# output_stage.net
KiCad netlist of a schematic drawn in EAGLE
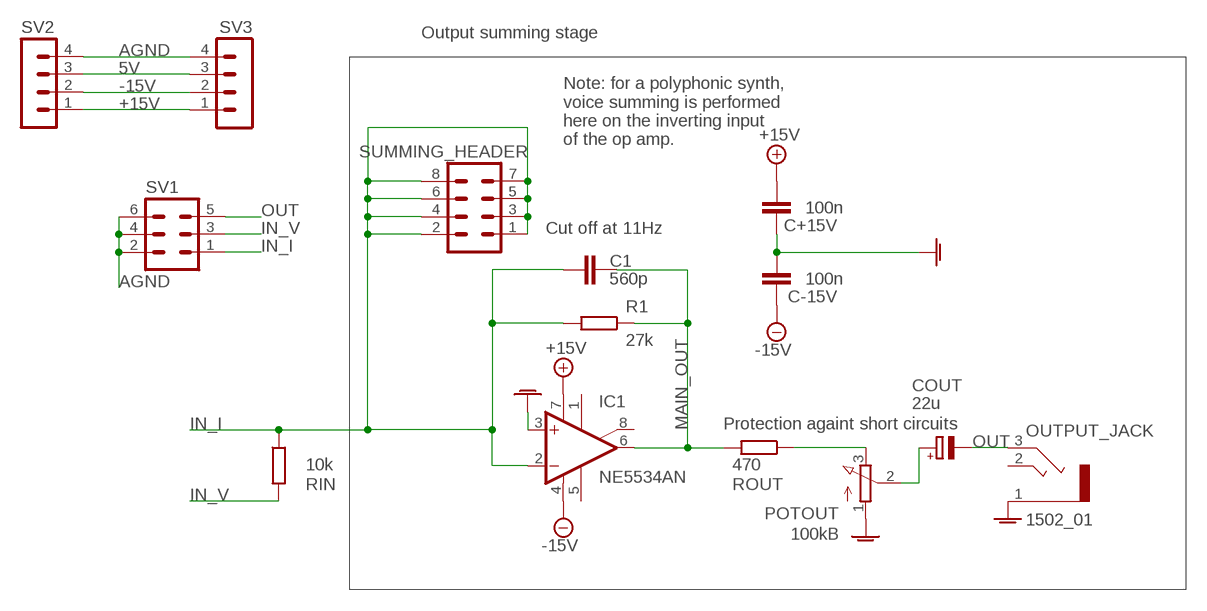
[diagram p0: schematic, sheet 1]

(export (version "E")
  (design (tool "Eeschema 10.0.6"))
  (components
    (comp (ref "C+15V")
      (value "100n")
      (footprint "eagle-import:C075-032X103")
      (libsource (lib "eagle-import") (part "C-EU075-032X103"))
    )
    (comp (ref "C-15V")
      (value "100n")
      (footprint "eagle-import:C075-032X103")
      (libsource (lib "eagle-import") (part "C-EU075-032X103"))
    )
    (comp (ref "C1")
      (value "560p")
      (footprint "eagle-import:C075-032X103")
      (libsource (lib "eagle-import") (part "C-EU075-032X103"))
    )
    (comp (ref "COUT")
      (value "22u")
      (footprint "eagle-import:B45181A")
      (libsource (lib "eagle-import") (part "CPOL-EUB45181A"))
    )
    (comp (ref "IC1")
      (value "NE5534AN")
      (footprint "eagle-import:DIL08")
      (libsource (lib "eagle-import") (part "NE5534NA"))
    )
    (comp (ref "OUTPUT_JACK")
      (value "1502_01")
      (footprint "eagle-import:1502_01")
      (libsource (lib "eagle-import") (part "1502_01"))
    )
    (comp (ref "POTOUT")
      (value "100kB")
      (footprint "eagle-import:3RP_1610N")
      (libsource (lib "eagle-import") (part "3RP/1610N"))
    )
    (comp (ref "R1")
      (value "27k")
      (footprint "eagle-import:0207_10")
      (libsource (lib "eagle-import") (part "R-EU_0207/10"))
    )
    (comp (ref "RIN")
      (value "10k")
      (footprint "eagle-import:0207_10")
      (libsource (lib "eagle-import") (part "R-EU_0207/10"))
    )
    (comp (ref "ROUT")
      (value "470")
      (footprint "eagle-import:0207_12")
      (libsource (lib "eagle-import") (part "R-EU_0207/12"))
    )
    (comp (ref "SUMMING_HEADER")
      (value "MA04-2")
      (footprint "eagle-import:MA04-2")
      (libsource (lib "eagle-import") (part "MA04-2"))
    )
    (comp (ref "SV1")
      (value "MA03-2")
      (footprint "eagle-import:MA03-2")
      (libsource (lib "eagle-import") (part "MA03-2"))
    )
    (comp (ref "SV2")
      (value "MA04-1")
      (footprint "eagle-import:MA04-1")
      (libsource (lib "eagle-import") (part "MA04-1"))
    )
    (comp (ref "SV3")
      (value "MA04-1")
      (footprint "eagle-import:MA04-1")
      (libsource (lib "eagle-import") (part "MA04-1"))
    )
  )
  (nets
    (net (code "1") (name "+15V") (class "Default")
      (node (ref "C+15V") (pin "2") (pinfunction "2_2") (pintype "passive"))
      (node (ref "IC1") (pin "7") (pinfunction "V+_7") (pintype "power_in"))
      (node (ref "SV2") (pin "1") (pinfunction "1_1") (pintype "passive"))
      (node (ref "SV3") (pin "1") (pinfunction "1_1") (pintype "passive"))
    )
    (net (code "2") (name "-15V") (class "Default")
      (node (ref "C-15V") (pin "1") (pinfunction "1_1") (pintype "passive"))
      (node (ref "IC1") (pin "4") (pinfunction "V-_4") (pintype "power_in"))
      (node (ref "SV2") (pin "2") (pinfunction "2_2") (pintype "passive"))
      (node (ref "SV3") (pin "2") (pinfunction "2_2") (pintype "passive"))
    )
    (net (code "3") (name "/5V") (class "Default")
      (node (ref "SV2") (pin "3") (pinfunction "3_3") (pintype "passive"))
      (node (ref "SV3") (pin "3") (pinfunction "3_3") (pintype "passive"))
    )
    (net (code "4") (name "/IN_I") (class "Default")
      (node (ref "C1") (pin "2") (pinfunction "2_2") (pintype "passive"))
      (node (ref "IC1") (pin "2") (pinfunction "-IN_2") (pintype "input"))
      (node (ref "R1") (pin "2") (pinfunction "2_2") (pintype "passive"))
      (node (ref "RIN") (pin "1") (pinfunction "1_1") (pintype "passive"))
      (node (ref "SUMMING_HEADER") (pin "1") (pinfunction "1_1") (pintype "passive"))
      (node (ref "SUMMING_HEADER") (pin "2") (pinfunction "2_2") (pintype "passive"))
      (node (ref "SUMMING_HEADER") (pin "3") (pinfunction "3_3") (pintype "passive"))
      (node (ref "SUMMING_HEADER") (pin "4") (pinfunction "4_4") (pintype "passive"))
      (node (ref "SUMMING_HEADER") (pin "5") (pinfunction "5_5") (pintype "passive"))
      (node (ref "SUMMING_HEADER") (pin "6") (pinfunction "6_6") (pintype "passive"))
      (node (ref "SUMMING_HEADER") (pin "7") (pinfunction "7_7") (pintype "passive"))
      (node (ref "SUMMING_HEADER") (pin "8") (pinfunction "8_8") (pintype "passive"))
      (node (ref "SV1") (pin "1") (pinfunction "1_1") (pintype "passive"))
    )
    (net (code "5") (name "/IN_V") (class "Default")
      (node (ref "RIN") (pin "2") (pinfunction "2_2") (pintype "passive"))
      (node (ref "SV1") (pin "3") (pinfunction "3_3") (pintype "passive"))
    )
    (net (code "6") (name "/MAIN_OUT") (class "Default")
      (node (ref "C1") (pin "1") (pinfunction "1_1") (pintype "passive"))
      (node (ref "IC1") (pin "6") (pinfunction "OUT_6") (pintype "output"))
      (node (ref "R1") (pin "1") (pinfunction "1_1") (pintype "passive"))
      (node (ref "ROUT") (pin "2") (pinfunction "2_2") (pintype "passive"))
    )
    (net (code "7") (name "/OUT") (class "Default")
      (node (ref "COUT") (pin "-") (pinfunction "-_-") (pintype "passive"))
      (node (ref "OUTPUT_JACK") (pin "3") (pinfunction "2_3") (pintype "passive"))
      (node (ref "SV1") (pin "5") (pinfunction "5_5") (pintype "passive"))
    )
    (net (code "8") (name "AGND") (class "Default")
      (node (ref "C+15V") (pin "1") (pinfunction "1_1") (pintype "passive"))
      (node (ref "C-15V") (pin "2") (pinfunction "2_2") (pintype "passive"))
      (node (ref "IC1") (pin "3") (pinfunction "+IN_3") (pintype "input"))
      (node (ref "OUTPUT_JACK") (pin "1") (pinfunction "1_1") (pintype "passive"))
      (node (ref "POTOUT") (pin "1") (pinfunction "A_1") (pintype "passive"))
      (node (ref "SV1") (pin "2") (pinfunction "2_2") (pintype "passive"))
      (node (ref "SV1") (pin "4") (pinfunction "4_4") (pintype "passive"))
      (node (ref "SV1") (pin "6") (pinfunction "6_6") (pintype "passive"))
      (node (ref "SV2") (pin "4") (pinfunction "4_4") (pintype "passive"))
      (node (ref "SV3") (pin "4") (pinfunction "4_4") (pintype "passive"))
    )
    (net (code "9") (name "Net-(POTOUT-E)") (class "Default")
      (node (ref "POTOUT") (pin "3") (pinfunction "E_3") (pintype "passive"))
      (node (ref "ROUT") (pin "1") (pinfunction "1_1") (pintype "passive"))
    )
    (net (code "10") (name "Net-(POTOUT-S)") (class "Default")
      (node (ref "COUT") (pin "+") (pinfunction "+_+") (pintype "passive"))
      (node (ref "POTOUT") (pin "2") (pinfunction "S_2") (pintype "passive"))
    )
    (net (code "11") (name "unconnected-(IC1-CMP-Pad5)") (class "Default")
      (node (ref "IC1") (pin "5") (pinfunction "CMP_5") (pintype "passive"))
    )
    (net (code "12") (name "unconnected-(IC1-ON-Pad1)") (class "Default")
      (node (ref "IC1") (pin "1") (pinfunction "ON_1") (pintype "passive"))
    )
    (net (code "13") (name "unconnected-(IC1-ON{slash}CMP-Pad8)") (class "Default")
      (node (ref "IC1") (pin "8") (pinfunction "ON/CMP_8") (pintype "passive"))
    )
    (net (code "14") (name "unconnected-(OUTPUT_JACK-3-Pad2)") (class "Default")
      (node (ref "OUTPUT_JACK") (pin "2") (pinfunction "3_2") (pintype "passive"))
    )
  )
)
